# ADS7952.net
KiCad netlist of a schematic drawn in Altium Designer
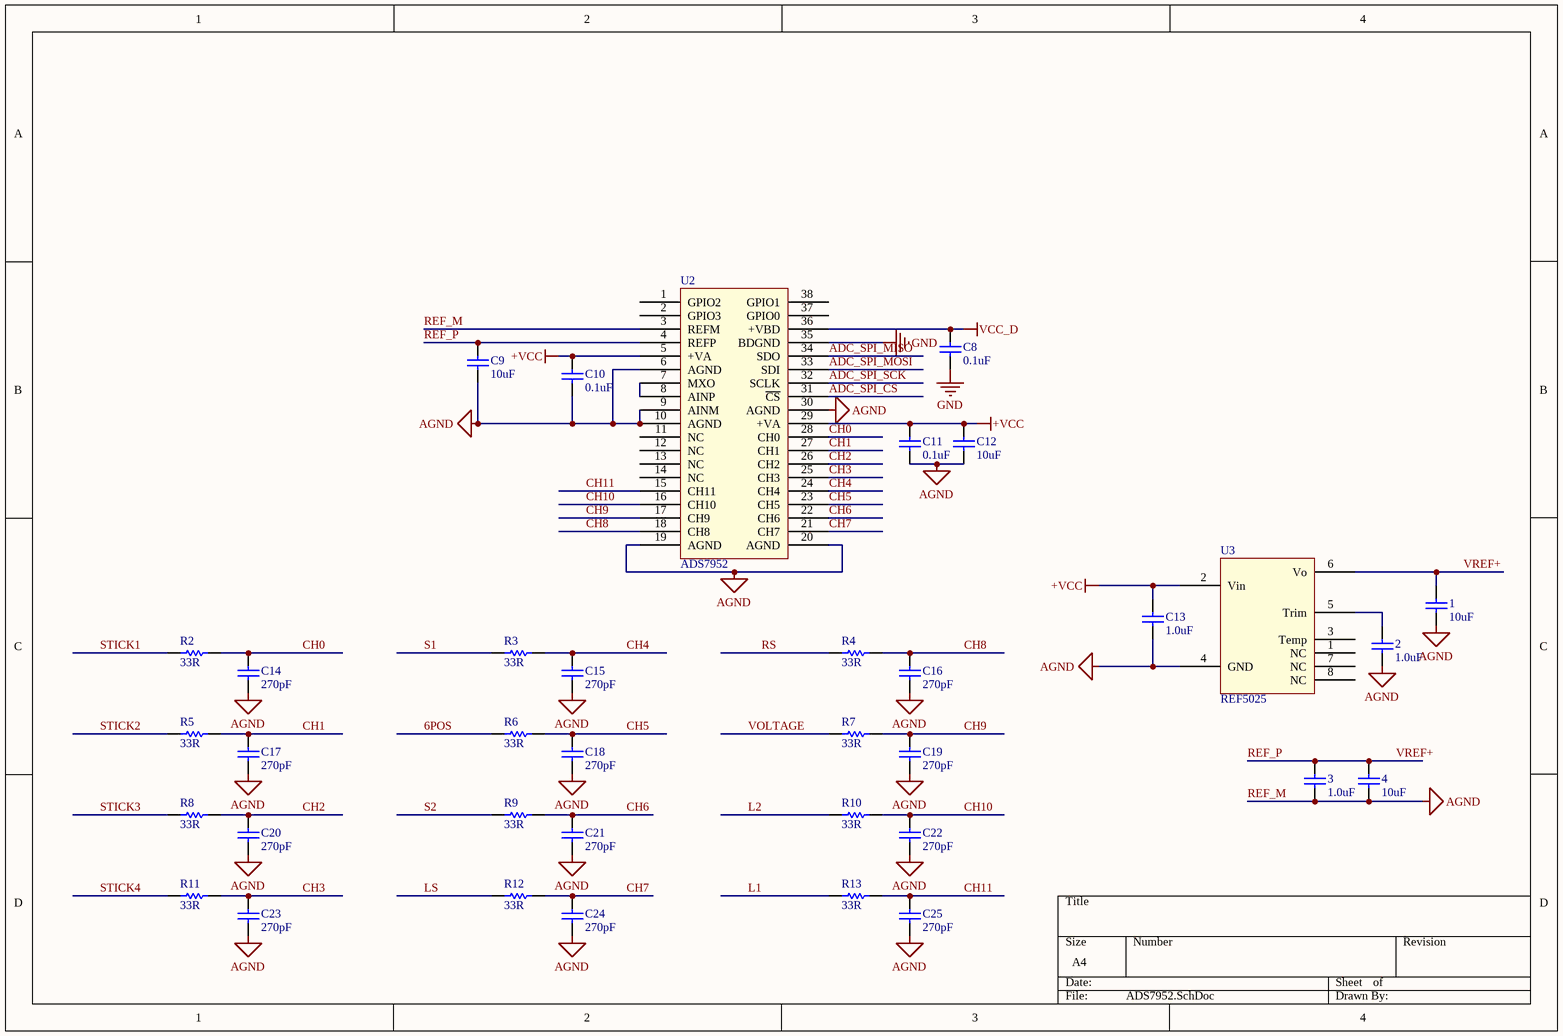
[diagram p0: ADS7952.SchDoc]

(export (version "E")
  (design (tool "Eeschema 10.0.6"))
  (components
    (comp (ref "1")
      (value "10uF")
      (footprint "0603C")
      (description "电容")
      (libsource (lib "常用元件") (part "CAP-0603"))
    )
    (comp (ref "2")
      (value "1.0uF")
      (footprint "0603C")
      (description "电容")
      (libsource (lib "常用元件") (part "CAP-0603"))
    )
    (comp (ref "3")
      (value "1.0uF")
      (footprint "0603C")
      (description "电容")
      (libsource (lib "常用元件") (part "CAP-0603"))
    )
    (comp (ref "4")
      (value "10uF")
      (footprint "0603C")
      (description "电容")
      (libsource (lib "常用元件") (part "CAP-0603"))
    )
    (comp (ref "C8")
      (value "0.1uF")
      (footprint "0603C")
      (description "电容")
      (libsource (lib "常用元件") (part "CAP-0603"))
    )
    (comp (ref "C9")
      (value "10uF")
      (footprint "0603C")
      (description "电容")
      (libsource (lib "常用元件") (part "CAP-0603"))
    )
    (comp (ref "C10")
      (value "0.1uF")
      (footprint "0603C")
      (description "电容")
      (libsource (lib "常用元件") (part "CAP-0603"))
    )
    (comp (ref "C11")
      (value "0.1uF")
      (footprint "0603C")
      (description "电容")
      (libsource (lib "常用元件") (part "CAP-0603"))
    )
    (comp (ref "C12")
      (value "10uF")
      (footprint "0603C")
      (description "电容")
      (libsource (lib "常用元件") (part "CAP-0603"))
    )
    (comp (ref "C13")
      (value "1.0uF")
      (footprint "0603C")
      (description "电容")
      (libsource (lib "常用元件") (part "CAP-0603"))
    )
    (comp (ref "C14")
      (value "270pF")
      (footprint "0603C")
      (description "电容")
      (libsource (lib "常用元件") (part "CAP-0603"))
    )
    (comp (ref "C15")
      (value "270pF")
      (footprint "0603C")
      (description "电容")
      (libsource (lib "常用元件") (part "CAP-0603"))
    )
    (comp (ref "C16")
      (value "270pF")
      (footprint "0603C")
      (description "电容")
      (libsource (lib "常用元件") (part "CAP-0603"))
    )
    (comp (ref "C17")
      (value "270pF")
      (footprint "0603C")
      (description "电容")
      (libsource (lib "常用元件") (part "CAP-0603"))
    )
    (comp (ref "C18")
      (value "270pF")
      (footprint "0603C")
      (description "电容")
      (libsource (lib "常用元件") (part "CAP-0603"))
    )
    (comp (ref "C19")
      (value "270pF")
      (footprint "0603C")
      (description "电容")
      (libsource (lib "常用元件") (part "CAP-0603"))
    )
    (comp (ref "C20")
      (value "270pF")
      (footprint "0603C")
      (description "电容")
      (libsource (lib "常用元件") (part "CAP-0603"))
    )
    (comp (ref "C21")
      (value "270pF")
      (footprint "0603C")
      (description "电容")
      (libsource (lib "常用元件") (part "CAP-0603"))
    )
    (comp (ref "C22")
      (value "270pF")
      (footprint "0603C")
      (description "电容")
      (libsource (lib "常用元件") (part "CAP-0603"))
    )
    (comp (ref "C23")
      (value "270pF")
      (footprint "0603C")
      (description "电容")
      (libsource (lib "常用元件") (part "CAP-0603"))
    )
    (comp (ref "C24")
      (value "270pF")
      (footprint "0603C")
      (description "电容")
      (libsource (lib "常用元件") (part "CAP-0603"))
    )
    (comp (ref "C25")
      (value "270pF")
      (footprint "0603C")
      (description "电容")
      (libsource (lib "常用元件") (part "CAP-0603"))
    )
    (comp (ref "R2")
      (value "33R")
      (footprint "0603R")
      (description "Resistance")
      (libsource (lib "常用元件") (part "RES-0603"))
    )
    (comp (ref "R3")
      (value "33R")
      (footprint "0603R")
      (description "Resistance")
      (libsource (lib "常用元件") (part "RES-0603"))
    )
    (comp (ref "R4")
      (value "33R")
      (footprint "0603R")
      (description "Resistance")
      (libsource (lib "常用元件") (part "RES-0603"))
    )
    (comp (ref "R5")
      (value "33R")
      (footprint "0603R")
      (description "Resistance")
      (libsource (lib "常用元件") (part "RES-0603"))
    )
    (comp (ref "R6")
      (value "33R")
      (footprint "0603R")
      (description "Resistance")
      (libsource (lib "常用元件") (part "RES-0603"))
    )
    (comp (ref "R7")
      (value "33R")
      (footprint "0603R")
      (description "Resistance")
      (libsource (lib "常用元件") (part "RES-0603"))
    )
    (comp (ref "R8")
      (value "33R")
      (footprint "0603R")
      (description "Resistance")
      (libsource (lib "常用元件") (part "RES-0603"))
    )
    (comp (ref "R9")
      (value "33R")
      (footprint "0603R")
      (description "Resistance")
      (libsource (lib "常用元件") (part "RES-0603"))
    )
    (comp (ref "R10")
      (value "33R")
      (footprint "0603R")
      (description "Resistance")
      (libsource (lib "常用元件") (part "RES-0603"))
    )
    (comp (ref "R11")
      (value "33R")
      (footprint "0603R")
      (description "Resistance")
      (libsource (lib "常用元件") (part "RES-0603"))
    )
    (comp (ref "R12")
      (value "33R")
      (footprint "0603R")
      (description "Resistance")
      (libsource (lib "常用元件") (part "RES-0603"))
    )
    (comp (ref "R13")
      (value "33R")
      (footprint "0603R")
      (description "Resistance")
      (libsource (lib "常用元件") (part "RES-0603"))
    )
    (comp (ref "U2") (value "ADS7952") (description "ADC采集芯片") (libsource (lib "常用元件") (part "ADS7952")))
    (comp (ref "U3") (value "REF5025") (description "基准源芯片") (libsource (lib "常用元件") (part "REF5025")))
  )
  (nets
    (net (code "1") (name "+VCC") (class "Default")
      (node (ref "C10") (pin "2") (pinfunction "2_2") (pintype "passive"))
      (node (ref "C11") (pin "2") (pinfunction "2_2") (pintype "passive"))
      (node (ref "C12") (pin "2") (pinfunction "2_2") (pintype "passive"))
      (node (ref "C13") (pin "2") (pinfunction "2_2") (pintype "passive"))
      (node (ref "U2") (pin "29") (pinfunction "+VA_29") (pintype "passive"))
      (node (ref "U2") (pin "5") (pinfunction "+VA_5") (pintype "passive"))
      (node (ref "U3") (pin "2") (pinfunction "Vin_2") (pintype "passive"))
    )
    (net (code "2") (name "/6POS") (class "Default")
      (node (ref "R6") (pin "1") (pinfunction "1_1") (pintype "passive"))
    )
    (net (code "3") (name "/ADC_SPI_CS") (class "Default")
      (node (ref "U2") (pin "31") (pinfunction "~{CS}_31") (pintype "passive"))
    )
    (net (code "4") (name "/ADC_SPI_MISO") (class "Default")
      (node (ref "U2") (pin "34") (pinfunction "SDO_34") (pintype "passive"))
    )
    (net (code "5") (name "/ADC_SPI_MOSI") (class "Default")
      (node (ref "U2") (pin "33") (pinfunction "SDI_33") (pintype "passive"))
    )
    (net (code "6") (name "/ADC_SPI_SCK") (class "Default")
      (node (ref "U2") (pin "32") (pinfunction "SCLK_32") (pintype "passive"))
    )
    (net (code "7") (name "/CH0") (class "Default")
      (node (ref "C14") (pin "2") (pinfunction "2_2") (pintype "passive"))
      (node (ref "R2") (pin "2") (pinfunction "2_2") (pintype "passive"))
      (node (ref "U2") (pin "28") (pinfunction "CH0_28") (pintype "passive"))
    )
    (net (code "8") (name "/CH1") (class "Default")
      (node (ref "C17") (pin "2") (pinfunction "2_2") (pintype "passive"))
      (node (ref "R5") (pin "2") (pinfunction "2_2") (pintype "passive"))
      (node (ref "U2") (pin "27") (pinfunction "CH1_27") (pintype "passive"))
    )
    (net (code "9") (name "/CH2") (class "Default")
      (node (ref "C20") (pin "2") (pinfunction "2_2") (pintype "passive"))
      (node (ref "R8") (pin "2") (pinfunction "2_2") (pintype "passive"))
      (node (ref "U2") (pin "26") (pinfunction "CH2_26") (pintype "passive"))
    )
    (net (code "10") (name "/CH3") (class "Default")
      (node (ref "C23") (pin "2") (pinfunction "2_2") (pintype "passive"))
      (node (ref "R11") (pin "2") (pinfunction "2_2") (pintype "passive"))
      (node (ref "U2") (pin "25") (pinfunction "CH3_25") (pintype "passive"))
    )
    (net (code "11") (name "/CH4") (class "Default")
      (node (ref "C15") (pin "2") (pinfunction "2_2") (pintype "passive"))
      (node (ref "R3") (pin "2") (pinfunction "2_2") (pintype "passive"))
      (node (ref "U2") (pin "24") (pinfunction "CH4_24") (pintype "passive"))
    )
    (net (code "12") (name "/CH5") (class "Default")
      (node (ref "C18") (pin "2") (pinfunction "2_2") (pintype "passive"))
      (node (ref "R6") (pin "2") (pinfunction "2_2") (pintype "passive"))
      (node (ref "U2") (pin "23") (pinfunction "CH5_23") (pintype "passive"))
    )
    (net (code "13") (name "/CH6") (class "Default")
      (node (ref "C21") (pin "2") (pinfunction "2_2") (pintype "passive"))
      (node (ref "R9") (pin "2") (pinfunction "2_2") (pintype "passive"))
      (node (ref "U2") (pin "22") (pinfunction "CH6_22") (pintype "passive"))
    )
    (net (code "14") (name "/CH7") (class "Default")
      (node (ref "C24") (pin "2") (pinfunction "2_2") (pintype "passive"))
      (node (ref "R12") (pin "2") (pinfunction "2_2") (pintype "passive"))
      (node (ref "U2") (pin "21") (pinfunction "CH7_21") (pintype "passive"))
    )
    (net (code "15") (name "/CH8") (class "Default")
      (node (ref "C16") (pin "2") (pinfunction "2_2") (pintype "passive"))
      (node (ref "R4") (pin "2") (pinfunction "2_2") (pintype "passive"))
      (node (ref "U2") (pin "18") (pinfunction "CH8_18") (pintype "passive"))
    )
    (net (code "16") (name "/CH9") (class "Default")
      (node (ref "C19") (pin "2") (pinfunction "2_2") (pintype "passive"))
      (node (ref "R7") (pin "2") (pinfunction "2_2") (pintype "passive"))
      (node (ref "U2") (pin "17") (pinfunction "CH9_17") (pintype "passive"))
    )
    (net (code "17") (name "/CH10") (class "Default")
      (node (ref "C22") (pin "2") (pinfunction "2_2") (pintype "passive"))
      (node (ref "R10") (pin "2") (pinfunction "2_2") (pintype "passive"))
      (node (ref "U2") (pin "16") (pinfunction "CH10_16") (pintype "passive"))
    )
    (net (code "18") (name "/CH11") (class "Default")
      (node (ref "C25") (pin "2") (pinfunction "2_2") (pintype "passive"))
      (node (ref "R13") (pin "2") (pinfunction "2_2") (pintype "passive"))
      (node (ref "U2") (pin "15") (pinfunction "CH11_15") (pintype "passive"))
    )
    (net (code "19") (name "/L1") (class "Default")
      (node (ref "R13") (pin "1") (pinfunction "1_1") (pintype "passive"))
    )
    (net (code "20") (name "/L2") (class "Default")
      (node (ref "R10") (pin "1") (pinfunction "1_1") (pintype "passive"))
    )
    (net (code "21") (name "/LS") (class "Default")
      (node (ref "R12") (pin "1") (pinfunction "1_1") (pintype "passive"))
    )
    (net (code "22") (name "/REF_P") (class "Default")
      (node (ref "1") (pin "2") (pinfunction "2_2") (pintype "passive"))
      (node (ref "3") (pin "2") (pinfunction "2_2") (pintype "passive"))
      (node (ref "4") (pin "2") (pinfunction "2_2") (pintype "passive"))
      (node (ref "C9") (pin "2") (pinfunction "2_2") (pintype "passive"))
      (node (ref "U2") (pin "4") (pinfunction "REFP_4") (pintype "passive"))
      (node (ref "U3") (pin "6") (pinfunction "Vo_6") (pintype "passive"))
    )
    (net (code "23") (name "/RS") (class "Default")
      (node (ref "R4") (pin "1") (pinfunction "1_1") (pintype "passive"))
    )
    (net (code "24") (name "/S1") (class "Default")
      (node (ref "R3") (pin "1") (pinfunction "1_1") (pintype "passive"))
    )
    (net (code "25") (name "/S2") (class "Default")
      (node (ref "R9") (pin "1") (pinfunction "1_1") (pintype "passive"))
    )
    (net (code "26") (name "/STICK1") (class "Default")
      (node (ref "R2") (pin "1") (pinfunction "1_1") (pintype "passive"))
    )
    (net (code "27") (name "/STICK2") (class "Default")
      (node (ref "R5") (pin "1") (pinfunction "1_1") (pintype "passive"))
    )
    (net (code "28") (name "/STICK3") (class "Default")
      (node (ref "R8") (pin "1") (pinfunction "1_1") (pintype "passive"))
    )
    (net (code "29") (name "/STICK4") (class "Default")
      (node (ref "R11") (pin "1") (pinfunction "1_1") (pintype "passive"))
    )
    (net (code "30") (name "/VOLTAGE") (class "Default")
      (node (ref "R7") (pin "1") (pinfunction "1_1") (pintype "passive"))
    )
    (net (code "31") (name "AGND") (class "Default")
      (node (ref "1") (pin "1") (pinfunction "1_1") (pintype "passive"))
      (node (ref "2") (pin "1") (pinfunction "1_1") (pintype "passive"))
      (node (ref "3") (pin "1") (pinfunction "1_1") (pintype "passive"))
      (node (ref "4") (pin "1") (pinfunction "1_1") (pintype "passive"))
      (node (ref "C10") (pin "1") (pinfunction "1_1") (pintype "passive"))
      (node (ref "C11") (pin "1") (pinfunction "1_1") (pintype "passive"))
      (node (ref "C12") (pin "1") (pinfunction "1_1") (pintype "passive"))
      (node (ref "C13") (pin "1") (pinfunction "1_1") (pintype "passive"))
      (node (ref "C14") (pin "1") (pinfunction "1_1") (pintype "passive"))
      (node (ref "C15") (pin "1") (pinfunction "1_1") (pintype "passive"))
      (node (ref "C16") (pin "1") (pinfunction "1_1") (pintype "passive"))
      (node (ref "C17") (pin "1") (pinfunction "1_1") (pintype "passive"))
      (node (ref "C18") (pin "1") (pinfunction "1_1") (pintype "passive"))
      (node (ref "C19") (pin "1") (pinfunction "1_1") (pintype "passive"))
      (node (ref "C20") (pin "1") (pinfunction "1_1") (pintype "passive"))
      (node (ref "C21") (pin "1") (pinfunction "1_1") (pintype "passive"))
      (node (ref "C22") (pin "1") (pinfunction "1_1") (pintype "passive"))
      (node (ref "C23") (pin "1") (pinfunction "1_1") (pintype "passive"))
      (node (ref "C24") (pin "1") (pinfunction "1_1") (pintype "passive"))
      (node (ref "C25") (pin "1") (pinfunction "1_1") (pintype "passive"))
      (node (ref "C9") (pin "1") (pinfunction "1_1") (pintype "passive"))
      (node (ref "U2") (pin "10") (pinfunction "AGND_10") (pintype "passive"))
      (node (ref "U2") (pin "19") (pinfunction "AGND_19") (pintype "passive"))
      (node (ref "U2") (pin "20") (pinfunction "AGND_20") (pintype "passive"))
      (node (ref "U2") (pin "3") (pinfunction "REFM_3") (pintype "passive"))
      (node (ref "U2") (pin "30") (pinfunction "AGND_30") (pintype "passive"))
      (node (ref "U2") (pin "6") (pinfunction "AGND_6") (pintype "passive"))
      (node (ref "U2") (pin "9") (pinfunction "AINM_9") (pintype "passive"))
      (node (ref "U3") (pin "4") (pinfunction "GND_4") (pintype "passive"))
    )
    (net (code "32") (name "GND") (class "Default")
      (node (ref "C8") (pin "1") (pinfunction "1_1") (pintype "passive"))
      (node (ref "U2") (pin "35") (pinfunction "BDGND_35") (pintype "passive"))
    )
    (net (code "33") (name "Net-(U2-AINP)") (class "Default")
      (node (ref "U2") (pin "7") (pinfunction "MXO_7") (pintype "passive"))
      (node (ref "U2") (pin "8") (pinfunction "AINP_8") (pintype "passive"))
    )
    (net (code "34") (name "Net-(U3-Trim)") (class "Default")
      (node (ref "2") (pin "2") (pinfunction "2_2") (pintype "passive"))
      (node (ref "U3") (pin "5") (pinfunction "Trim_5") (pintype "passive"))
    )
    (net (code "35") (name "VCC_D") (class "Default")
      (node (ref "C8") (pin "2") (pinfunction "2_2") (pintype "passive"))
      (node (ref "U2") (pin "36") (pinfunction "+VBD_36") (pintype "passive"))
    )
    (net (code "36") (name "unconnected-(U2-GPIO0-Pad37)") (class "Default")
      (node (ref "U2") (pin "37") (pinfunction "GPIO0_37") (pintype "passive"))
    )
    (net (code "37") (name "unconnected-(U2-GPIO1-Pad38)") (class "Default")
      (node (ref "U2") (pin "38") (pinfunction "GPIO1_38") (pintype "passive"))
    )
    (net (code "38") (name "unconnected-(U2-GPIO2-Pad1)") (class "Default")
      (node (ref "U2") (pin "1") (pinfunction "GPIO2_1") (pintype "passive"))
    )
    (net (code "39") (name "unconnected-(U2-GPIO3-Pad2)") (class "Default")
      (node (ref "U2") (pin "2") (pinfunction "GPIO3_2") (pintype "passive"))
    )
    (net (code "40") (name "unconnected-(U2-NC-Pad11)") (class "Default")
      (node (ref "U2") (pin "11") (pinfunction "NC_11") (pintype "passive"))
    )
    (net (code "41") (name "unconnected-(U2-NC-Pad12)") (class "Default")
      (node (ref "U2") (pin "12") (pinfunction "NC_12") (pintype "passive"))
    )
    (net (code "42") (name "unconnected-(U2-NC-Pad13)") (class "Default")
      (node (ref "U2") (pin "13") (pinfunction "NC_13") (pintype "passive"))
    )
    (net (code "43") (name "unconnected-(U2-NC-Pad14)") (class "Default")
      (node (ref "U2") (pin "14") (pinfunction "NC_14") (pintype "passive"))
    )
    (net (code "44") (name "unconnected-(U3-NC-Pad1)") (class "Default")
      (node (ref "U3") (pin "1") (pinfunction "NC_1") (pintype "passive"))
    )
    (net (code "45") (name "unconnected-(U3-NC-Pad7)") (class "Default")
      (node (ref "U3") (pin "7") (pinfunction "NC_7") (pintype "passive"))
    )
    (net (code "46") (name "unconnected-(U3-NC-Pad8)") (class "Default")
      (node (ref "U3") (pin "8") (pinfunction "NC_8") (pintype "passive"))
    )
    (net (code "47") (name "unconnected-(U3-Temp-Pad3)") (class "Default")
      (node (ref "U3") (pin "3") (pinfunction "Temp_3") (pintype "passive"))
    )
  )
)
